# Decodificador_de_ppm.net
KiCad netlist of a schematic drawn in EAGLE
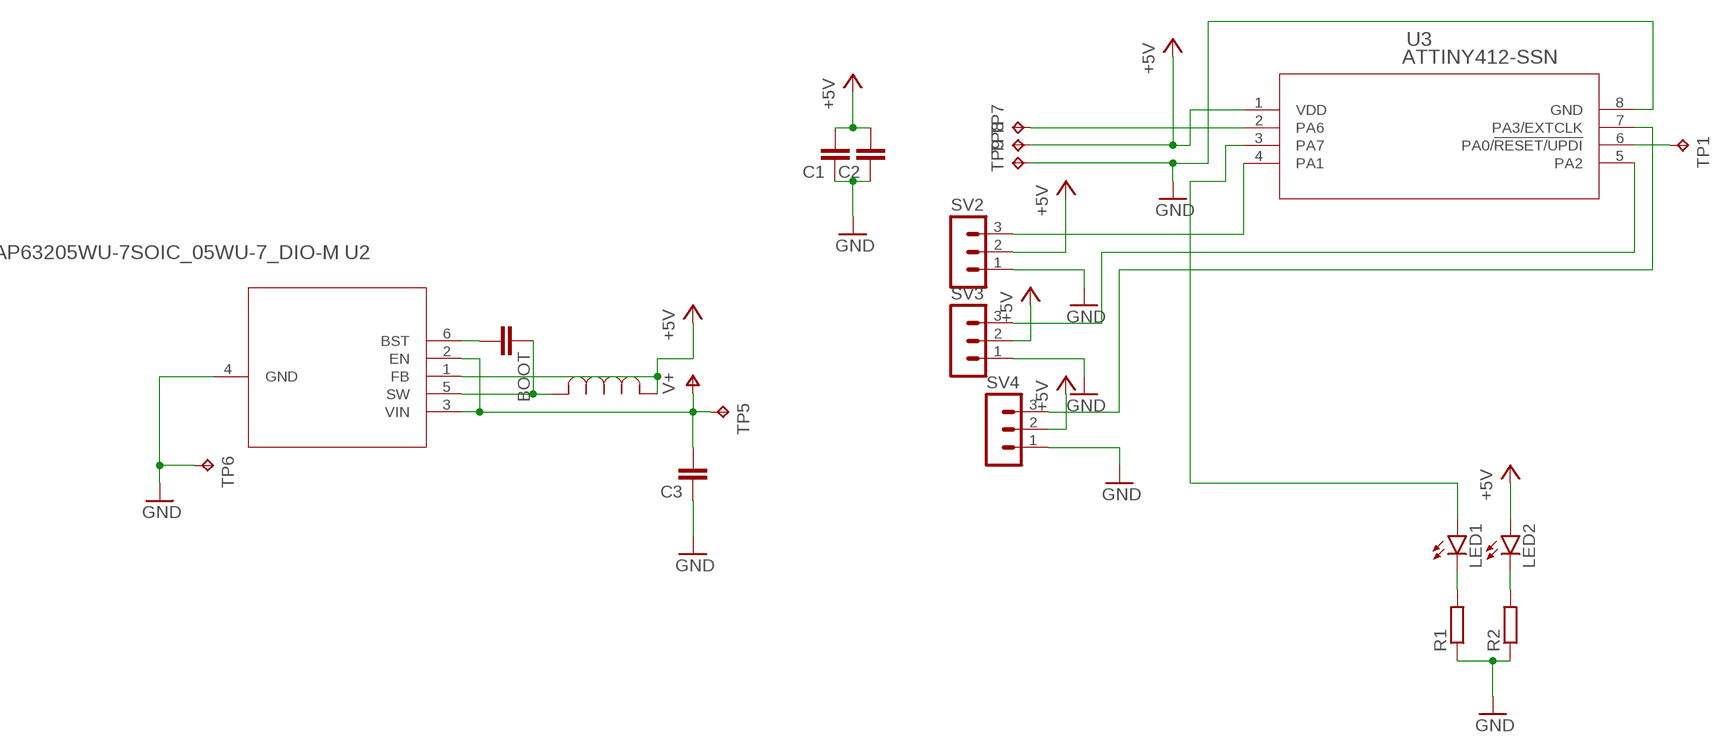
[diagram p0: schematic, sheet 1]

(export (version "E")
  (design (tool "Eeschema 10.0.6"))
  (components
    (comp (ref "BOOT")
      (value "C-EUC0402")
      (footprint "eagle-import:C0402")
      (libsource (lib "eagle-import") (part "C-EUC0402"))
    )
    (comp (ref "C1")
      (value "C-EUC0805")
      (footprint "eagle-import:C0805")
      (libsource (lib "eagle-import") (part "C-EUC0805"))
    )
    (comp (ref "C2")
      (value "C-EUC0805")
      (footprint "eagle-import:C0805")
      (libsource (lib "eagle-import") (part "C-EUC0805"))
    )
    (comp (ref "C3")
      (value "C-EUC0805")
      (footprint "eagle-import:C0805")
      (libsource (lib "eagle-import") (part "C-EUC0805"))
    )
    (comp (ref "LED1")
      (value "LEDCHIP-LED0603")
      (footprint "eagle-import:CHIP-LED0603")
      (libsource (lib "eagle-import") (part "LEDCHIP-LED0603"))
    )
    (comp (ref "LED2")
      (value "LEDCHIP-LED0603")
      (footprint "eagle-import:CHIP-LED0603")
      (libsource (lib "eagle-import") (part "LEDCHIP-LED0603"))
    )
    (comp (ref "R1")
      (value "R-EU_R0805")
      (footprint "eagle-import:R0805")
      (libsource (lib "eagle-import") (part "R-EU_R0805"))
    )
    (comp (ref "R2")
      (value "R-EU_R0805")
      (footprint "eagle-import:R0805")
      (libsource (lib "eagle-import") (part "R-EU_R0805"))
    )
    (comp (ref "SV2")
      (value "MA03-1")
      (footprint "eagle-import:MA03-1")
      (libsource (lib "eagle-import") (part "MA03-1"))
    )
    (comp (ref "SV3")
      (value "MA03-1")
      (footprint "eagle-import:MA03-1")
      (libsource (lib "eagle-import") (part "MA03-1"))
    )
    (comp (ref "SV4")
      (value "MA03-1")
      (footprint "eagle-import:MA03-1")
      (libsource (lib "eagle-import") (part "MA03-1"))
    )
    (comp (ref "TP1")
      (value "TPB1,27")
      (footprint "eagle-import:B1,27")
      (libsource (lib "eagle-import") (part "TPB1,27"))
    )
    (comp (ref "TP5")
      (value "TPTP19SQ")
      (footprint "eagle-import:TP19SQ")
      (libsource (lib "eagle-import") (part "TPTP19SQ"))
    )
    (comp (ref "TP6")
      (value "TPTP19SQ")
      (footprint "eagle-import:TP19SQ")
      (libsource (lib "eagle-import") (part "TPTP19SQ"))
    )
    (comp (ref "TP7")
      (value "TPTP19SQ")
      (footprint "eagle-import:TP19SQ")
      (libsource (lib "eagle-import") (part "TPTP19SQ"))
    )
    (comp (ref "TP8")
      (value "TPTP19SQ")
      (footprint "eagle-import:TP19SQ")
      (libsource (lib "eagle-import") (part "TPTP19SQ"))
    )
    (comp (ref "TP9")
      (value "TPTP19SQ")
      (footprint "eagle-import:TP19SQ")
      (libsource (lib "eagle-import") (part "TPTP19SQ"))
    )
    (comp (ref "U$2")
      (value "INDUCTOR4.7")
      (footprint "eagle-import:IND_NRS5030T100MMGJ_TAY")
      (libsource (lib "eagle-import") (part "INDUCTOR4.7"))
    )
    (comp (ref "U2")
      (value "AP63205WU-7SOIC_05WU-7_DIO-M")
      (footprint "eagle-import:SOIC_05WU-7_DIO-M")
      (fields
        (field (name "MANUFACTURER_PART_NUMBER") "AP63205WU-7")
        (field (name "COPYRIGHT") "Copyright (C) 2018 Accelerated Designs. All rights reserved")
      )
      (libsource (lib "eagle-import") (part "AP63205WU-7SOIC_05WU-7_DIO-M"))
    )
    (comp (ref "U3")
      (value "ATTINY412-SSN")
      (footprint "eagle-import:SOIC8_SA_SST_MCH")
      (fields (field (name "COPYRIGHT") "Copyright (C) 2018 Accelerated Designs. All rights reserved"))
      (libsource (lib "eagle-import") (part "ATTINY412-SSN"))
    )
  )
  (nets
    (net (code "1") (name "+5V") (class "Default")
      (node (ref "C1") (pin "2") (pinfunction "2_2") (pintype "passive"))
      (node (ref "C2") (pin "2") (pinfunction "2_2") (pintype "passive"))
      (node (ref "LED2") (pin "A") (pinfunction "A_A") (pintype "passive"))
      (node (ref "SV2") (pin "2") (pinfunction "2_2") (pintype "passive"))
      (node (ref "SV3") (pin "2") (pinfunction "2_2") (pintype "passive"))
      (node (ref "SV4") (pin "2") (pinfunction "2_2") (pintype "passive"))
      (node (ref "TP8") (pin "TP") (pinfunction "TP_TP") (pintype "input"))
      (node (ref "U$2") (pin "1") (pinfunction "1_1") (pintype "passive"))
      (node (ref "U2") (pin "1") (pinfunction "FB_1") (pintype "passive"))
      (node (ref "U3") (pin "1") (pinfunction "VDD_1") (pintype "power_in"))
    )
    (net (code "2") (name "GND") (class "Default")
      (node (ref "C1") (pin "1") (pinfunction "1_1") (pintype "passive"))
      (node (ref "C2") (pin "1") (pinfunction "1_1") (pintype "passive"))
      (node (ref "C3") (pin "1") (pinfunction "1_1") (pintype "passive"))
      (node (ref "R1") (pin "1") (pinfunction "1_1") (pintype "passive"))
      (node (ref "R2") (pin "1") (pinfunction "1_1") (pintype "passive"))
      (node (ref "SV2") (pin "1") (pinfunction "1_1") (pintype "passive"))
      (node (ref "SV3") (pin "1") (pinfunction "1_1") (pintype "passive"))
      (node (ref "SV4") (pin "1") (pinfunction "1_1") (pintype "passive"))
      (node (ref "TP6") (pin "TP") (pinfunction "TP_TP") (pintype "input"))
      (node (ref "TP9") (pin "TP") (pinfunction "TP_TP") (pintype "input"))
      (node (ref "U2") (pin "4") (pinfunction "GND_4") (pintype "passive"))
      (node (ref "U3") (pin "8") (pinfunction "GND_8") (pintype "passive"))
    )
    (net (code "3") (name "Net-(LED1-PadC)") (class "Default")
      (node (ref "LED1") (pin "C") (pinfunction "C_C") (pintype "passive"))
      (node (ref "R1") (pin "2") (pinfunction "2_2") (pintype "passive"))
    )
    (net (code "4") (name "Net-(LED2-PadC)") (class "Default")
      (node (ref "LED2") (pin "C") (pinfunction "C_C") (pintype "passive"))
      (node (ref "R2") (pin "2") (pinfunction "2_2") (pintype "passive"))
    )
    (net (code "5") (name "Net-(U2-BST)") (class "Default")
      (node (ref "BOOT") (pin "2") (pinfunction "2_2") (pintype "passive"))
      (node (ref "U2") (pin "6") (pinfunction "BST_6") (pintype "passive"))
    )
    (net (code "6") (name "Net-(U2-SW)") (class "Default")
      (node (ref "BOOT") (pin "1") (pinfunction "1_1") (pintype "passive"))
      (node (ref "U$2") (pin "2") (pinfunction "2_2") (pintype "passive"))
      (node (ref "U2") (pin "5") (pinfunction "SW_5") (pintype "passive"))
    )
    (net (code "7") (name "Net-(U3-PA0{slash}~{RESET{slash}UPDI})") (class "Default")
      (node (ref "TP1") (pin "TP") (pinfunction "TP_TP") (pintype "input"))
      (node (ref "U3") (pin "6") (pinfunction "PA0/~{RESET/UPDI}_6") (pintype "bidirectional"))
    )
    (net (code "8") (name "Net-(U3-PA1)") (class "Default")
      (node (ref "SV2") (pin "3") (pinfunction "3_3") (pintype "passive"))
      (node (ref "U3") (pin "4") (pinfunction "PA1_4") (pintype "bidirectional"))
    )
    (net (code "9") (name "Net-(U3-PA2)") (class "Default")
      (node (ref "SV3") (pin "3") (pinfunction "3_3") (pintype "passive"))
      (node (ref "U3") (pin "5") (pinfunction "PA2_5") (pintype "bidirectional"))
    )
    (net (code "10") (name "Net-(U3-PA3{slash}EXTCLK)") (class "Default")
      (node (ref "SV4") (pin "3") (pinfunction "3_3") (pintype "passive"))
      (node (ref "U3") (pin "7") (pinfunction "PA3/EXTCLK_7") (pintype "bidirectional"))
    )
    (net (code "11") (name "Net-(U3-PA6)") (class "Default")
      (node (ref "TP7") (pin "TP") (pinfunction "TP_TP") (pintype "input"))
      (node (ref "U3") (pin "2") (pinfunction "PA6_2") (pintype "bidirectional"))
    )
    (net (code "12") (name "Net-(U3-PA7)") (class "Default")
      (node (ref "LED1") (pin "A") (pinfunction "A_A") (pintype "passive"))
      (node (ref "U3") (pin "3") (pinfunction "PA7_3") (pintype "bidirectional"))
    )
    (net (code "13") (name "V+") (class "Default")
      (node (ref "C3") (pin "2") (pinfunction "2_2") (pintype "passive"))
      (node (ref "TP5") (pin "TP") (pinfunction "TP_TP") (pintype "input"))
      (node (ref "U2") (pin "2") (pinfunction "EN_2") (pintype "passive"))
      (node (ref "U2") (pin "3") (pinfunction "VIN_3") (pintype "passive"))
    )
  )
)
